# Hypnos_V2.net
KiCad netlist of a schematic drawn in EAGLE
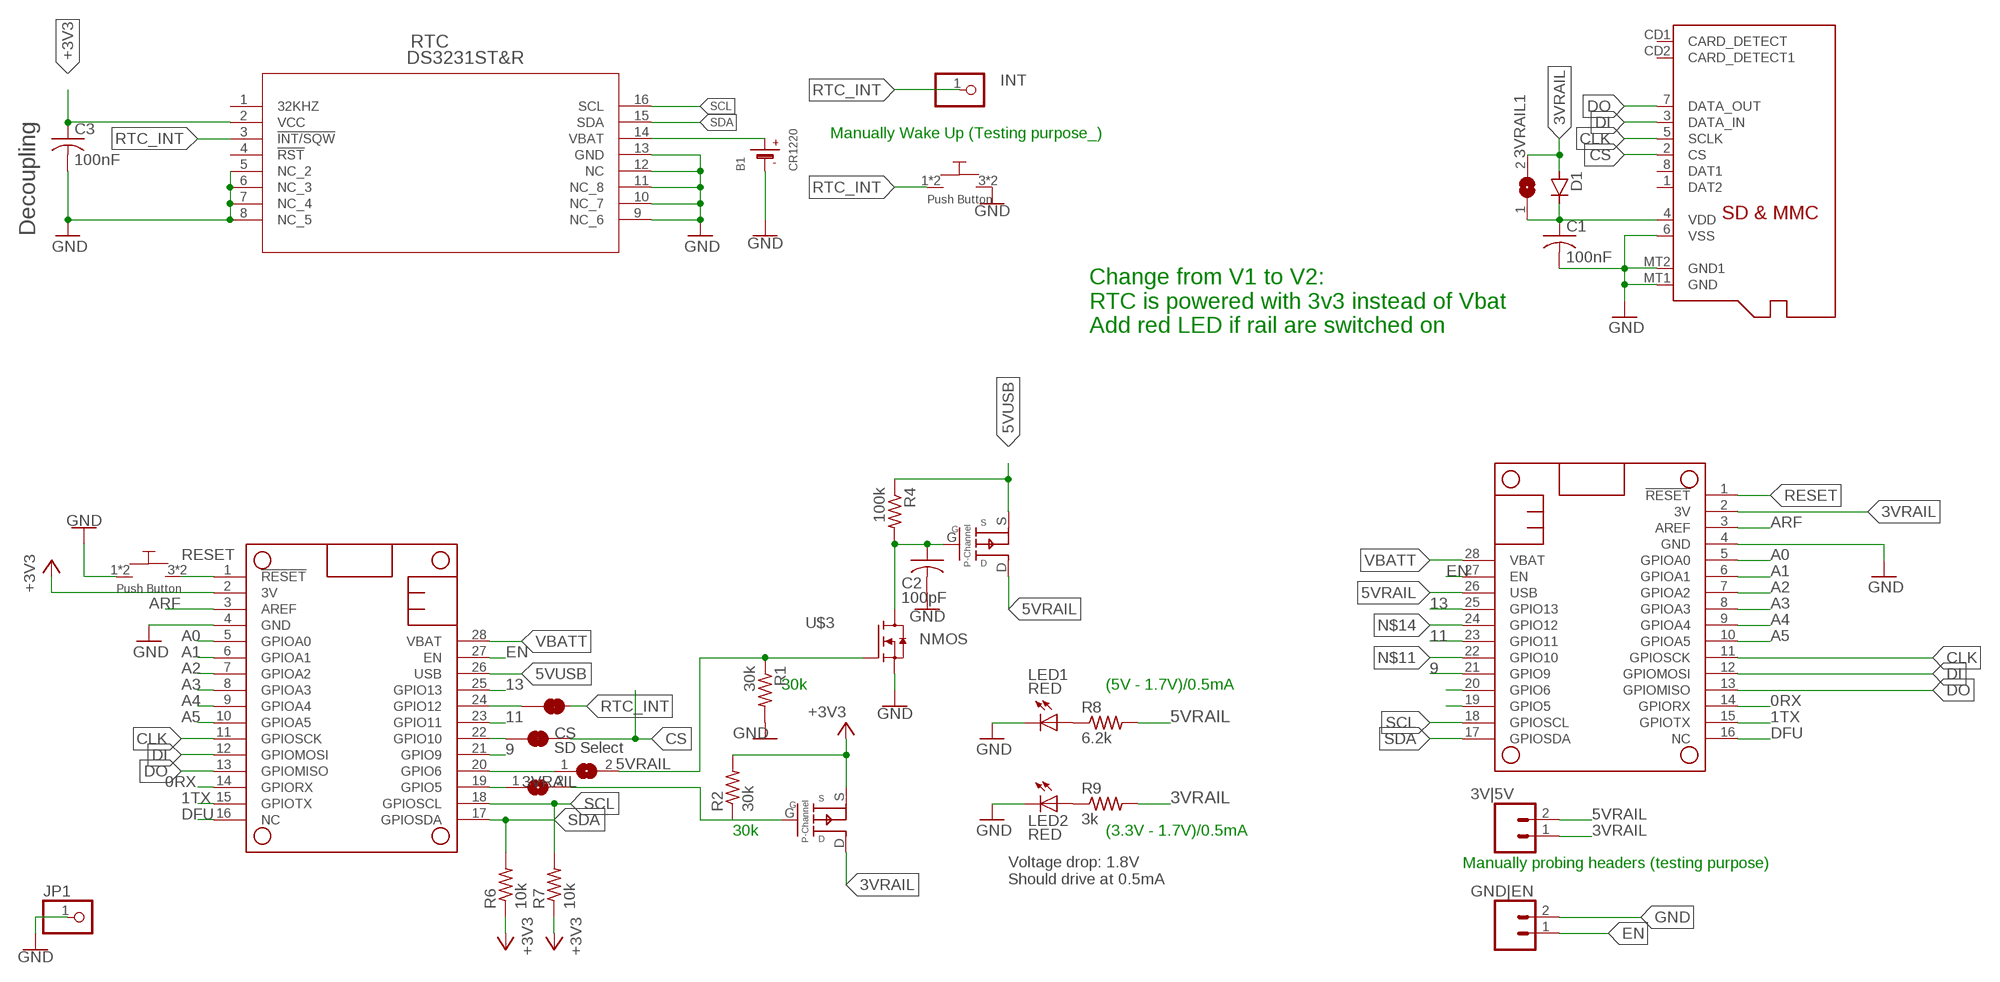
[diagram p0: schematic, sheet 1]

(export (version "E")
  (design (tool "Eeschema 10.0.6"))
  (components
    (comp (ref "3VRAIL")
      (value "SJ")
      (footprint "eagle-import:SJ")
      (libsource (lib "eagle-import") (part "SJ"))
    )
    (comp (ref "3VRAIL1")
      (value "SJ")
      (footprint "eagle-import:SJ")
      (libsource (lib "eagle-import") (part "SJ"))
    )
    (comp (ref "3V|5V")
      (value "CONN_021X02_NO_SILK")
      (footprint "eagle-import:1X02_NO_SILK")
      (libsource (lib "eagle-import") (part "CONN_021X02_NO_SILK"))
    )
    (comp (ref "5VRAIL")
      (value "SJ")
      (footprint "eagle-import:SJ")
      (libsource (lib "eagle-import") (part "SJ"))
    )
    (comp (ref "B1")
      (value "CR1220")
      (footprint "eagle-import:CR1220")
      (libsource (lib "eagle-import") (part "BATTERYCR1220_SMT"))
    )
    (comp (ref "C1")
      (value "100nF")
      (footprint "eagle-import:C1206")
      (libsource (lib "eagle-import") (part "C-USC1206"))
    )
    (comp (ref "C2")
      (value "100pF")
      (footprint "eagle-import:C0805")
      (libsource (lib "eagle-import") (part "C-USC0805"))
    )
    (comp (ref "C3")
      (value "100nF")
      (footprint "eagle-import:C1206")
      (libsource (lib "eagle-import") (part "C-USC1206"))
    )
    (comp (ref "CS")
      (value "SD Select")
      (footprint "eagle-import:SMT-JUMPER_2_NC_TRACE_SILK")
      (libsource (lib "eagle-import") (part "JUMPER-SMT_2_NC_TRACE_SILK"))
    )
    (comp (ref "D1")
      (value "D-SOD123")
      (footprint "eagle-import:SOD123")
      (libsource (lib "eagle-import") (part "D-SOD123"))
    )
    (comp (ref "GND|EN")
      (value "CONN_021X02_NO_SILK")
      (footprint "eagle-import:1X02_NO_SILK")
      (libsource (lib "eagle-import") (part "CONN_021X02_NO_SILK"))
    )
    (comp (ref "INT")
      (value "PINHD-1X1CB")
      (footprint "eagle-import:1X01-CLEANBIG")
      (libsource (lib "eagle-import") (part "PINHD-1X1CB"))
    )
    (comp (ref "JP1")
      (value "PINHD-1X1CB")
      (footprint "eagle-import:1X01-CLEANBIG")
      (libsource (lib "eagle-import") (part "PINHD-1X1CB"))
    )
    (comp (ref "LED1")
      (value "RED")
      (footprint "eagle-import:CHIPLED_0805")
      (libsource (lib "eagle-import") (part "LEDCHIPLED_0805"))
    )
    (comp (ref "LED2")
      (value "RED")
      (footprint "eagle-import:CHIPLED_0805")
      (libsource (lib "eagle-import") (part "LEDCHIPLED_0805"))
    )
    (comp (ref "MICROSD")
      (value "MICROSD")
      (footprint "eagle-import:MICROSD")
      (libsource (lib "eagle-import") (part "MICROSD"))
    )
    (comp (ref "MS1")
      (value "FEATHERWING")
      (footprint "eagle-import:FEATHERWING")
      (libsource (lib "eagle-import") (part "powerboard_FEATHERWING"))
    )
    (comp (ref "MS2")
      (value "FEATHERWING")
      (footprint "eagle-import:FEATHERWING")
      (libsource (lib "eagle-import") (part "FEATHERWING"))
    )
    (comp (ref "PMOS1")
      (value "SSM3J3228R")
      (footprint "eagle-import:SOT-23-3")
      (libsource (lib "eagle-import") (part "SSM3J3228R"))
    )
    (comp (ref "PMOS2")
      (value "SSM3J3228R")
      (footprint "eagle-import:SOT-23-3")
      (libsource (lib "eagle-import") (part "SSM3J3228R"))
    )
    (comp (ref "R1")
      (value "30k")
      (footprint "eagle-import:RES_1206")
      (fields
        (field (name "DIGIKEY_PART_NUMBER") "WSLP-.05TR-ND")
        (field (name "MANUFACTURER") "Vishay Dale")
        (field (name "MPN") "WSLP1206R0500FEA")
        (field (name "CREATED_BY") "PCBLayout.com")
      )
      (libsource (lib "eagle-import") (part "WSLP1206R0500FEA"))
    )
    (comp (ref "R2")
      (value "30k")
      (footprint "eagle-import:RES_1206")
      (fields
        (field (name "DIGIKEY_PART_NUMBER") "WSLP-.05TR-ND")
        (field (name "MANUFACTURER") "Vishay Dale")
        (field (name "MPN") "WSLP1206R0500FEA")
        (field (name "CREATED_BY") "PCBLayout.com")
      )
      (libsource (lib "eagle-import") (part "WSLP1206R0500FEA"))
    )
    (comp (ref "R4")
      (value "100k")
      (footprint "eagle-import:RES_1206")
      (fields
        (field (name "DIGIKEY_PART_NUMBER") "WSLP-.05TR-ND")
        (field (name "MANUFACTURER") "Vishay Dale")
        (field (name "MPN") "WSLP1206R0500FEA")
        (field (name "CREATED_BY") "PCBLayout.com")
      )
      (libsource (lib "eagle-import") (part "WSLP1206R0500FEA"))
    )
    (comp (ref "R6")
      (value "10k")
      (footprint "eagle-import:RES_1206")
      (fields
        (field (name "DIGIKEY_PART_NUMBER") "WSLP-.05TR-ND")
        (field (name "MANUFACTURER") "Vishay Dale")
        (field (name "MPN") "WSLP1206R0500FEA")
        (field (name "CREATED_BY") "PCBLayout.com")
      )
      (libsource (lib "eagle-import") (part "WSLP1206R0500FEA"))
    )
    (comp (ref "R7")
      (value "10k")
      (footprint "eagle-import:RES_1206")
      (fields
        (field (name "DIGIKEY_PART_NUMBER") "WSLP-.05TR-ND")
        (field (name "MANUFACTURER") "Vishay Dale")
        (field (name "MPN") "WSLP1206R0500FEA")
        (field (name "CREATED_BY") "PCBLayout.com")
      )
      (libsource (lib "eagle-import") (part "WSLP1206R0500FEA"))
    )
    (comp (ref "R8")
      (value "6.2k")
      (footprint "eagle-import:RES_1206")
      (fields
        (field (name "DIGIKEY_PART_NUMBER") "WSLP-.05TR-ND")
        (field (name "MANUFACTURER") "Vishay Dale")
        (field (name "MPN") "WSLP1206R0500FEA")
        (field (name "CREATED_BY") "PCBLayout.com")
      )
      (libsource (lib "eagle-import") (part "WSLP1206R0500FEA"))
    )
    (comp (ref "R9")
      (value "3k")
      (footprint "eagle-import:RES_1206")
      (fields
        (field (name "DIGIKEY_PART_NUMBER") "WSLP-.05TR-ND")
        (field (name "MANUFACTURER") "Vishay Dale")
        (field (name "MPN") "WSLP1206R0500FEA")
        (field (name "CREATED_BY") "PCBLayout.com")
      )
      (libsource (lib "eagle-import") (part "WSLP1206R0500FEA"))
    )
    (comp (ref "RTC")
      (value "DS3231ST&R")
      (footprint "eagle-import:21-0042B_16")
      (fields (field (name "MANUFACTURER_PART_NUMBER") "DS3231S#T&R"))
      (libsource (lib "eagle-import") (part "DS3231ST&R"))
    )
    (comp (ref "RTC_INT")
      (value "JUMPER-SMT_2_NC_TRACE_SILK")
      (footprint "eagle-import:SMT-JUMPER_2_NC_TRACE_SILK")
      (libsource (lib "eagle-import") (part "JUMPER-SMT_2_NC_TRACE_SILK"))
    )
    (comp (ref "U$1")
      (value "PUSH_BUTTON")
      (footprint "eagle-import:PUSHBUTTON_SMD")
      (libsource (lib "eagle-import") (part "PUSH_BUTTON"))
    )
    (comp (ref "U$2")
      (value "PUSH_BUTTON")
      (footprint "eagle-import:PUSHBUTTON_SMD")
      (libsource (lib "eagle-import") (part "PUSH_BUTTON"))
    )
    (comp (ref "U$3")
      (value "NMOS")
      (footprint "eagle-import:SOT23-S")
      (libsource (lib "eagle-import") (part "NMOS"))
    )
  )
  (nets
    (net (code "1") (name "+3V3") (class "Default")
      (node (ref "C3") (pin "1") (pinfunction "1_1") (pintype "passive"))
      (node (ref "MS2") (pin "2") (pinfunction "3V_2") (pintype "power_in"))
      (node (ref "PMOS2") (pin "S") (pinfunction "S_S") (pintype "bidirectional"))
      (node (ref "R2") (pin "2") (pinfunction "2_2") (pintype "passive"))
      (node (ref "R6") (pin "1") (pinfunction "1_1") (pintype "passive"))
      (node (ref "R7") (pin "1") (pinfunction "1_1") (pintype "passive"))
      (node (ref "RTC") (pin "2") (pinfunction "VCC_2") (pintype "power_in"))
    )
    (net (code "2") (name "/0RX") (class "Default")
      (node (ref "MS1") (pin "14") (pinfunction "GPIORX_14") (pintype "bidirectional"))
      (node (ref "MS2") (pin "14") (pinfunction "GPIORX_14") (pintype "bidirectional"))
    )
    (net (code "3") (name "/1TX") (class "Default")
      (node (ref "MS1") (pin "15") (pinfunction "GPIOTX_15") (pintype "bidirectional"))
      (node (ref "MS2") (pin "15") (pinfunction "GPIOTX_15") (pintype "bidirectional"))
    )
    (net (code "4") (name "/9") (class "Default")
      (node (ref "MS1") (pin "21") (pinfunction "GPIO9_21") (pintype "bidirectional"))
      (node (ref "MS2") (pin "21") (pinfunction "GPIO9_21") (pintype "bidirectional"))
    )
    (net (code "5") (name "/11") (class "Default")
      (node (ref "MS1") (pin "23") (pinfunction "GPIO11_23") (pintype "bidirectional"))
      (node (ref "MS2") (pin "23") (pinfunction "GPIO11_23") (pintype "bidirectional"))
    )
    (net (code "6") (name "/13") (class "Default")
      (node (ref "MS1") (pin "25") (pinfunction "GPIO13_25") (pintype "bidirectional"))
      (node (ref "MS2") (pin "25") (pinfunction "GPIO13_25") (pintype "bidirectional"))
    )
    (net (code "7") (name "/A0") (class "Default")
      (node (ref "MS1") (pin "5") (pinfunction "GPIOA0_5") (pintype "bidirectional"))
      (node (ref "MS2") (pin "5") (pinfunction "GPIOA0_5") (pintype "bidirectional"))
    )
    (net (code "8") (name "/A1") (class "Default")
      (node (ref "MS1") (pin "6") (pinfunction "GPIOA1_6") (pintype "bidirectional"))
      (node (ref "MS2") (pin "6") (pinfunction "GPIOA1_6") (pintype "bidirectional"))
    )
    (net (code "9") (name "/A2") (class "Default")
      (node (ref "MS1") (pin "7") (pinfunction "GPIOA2_7") (pintype "bidirectional"))
      (node (ref "MS2") (pin "7") (pinfunction "GPIOA2_7") (pintype "bidirectional"))
    )
    (net (code "10") (name "/A3") (class "Default")
      (node (ref "MS1") (pin "8") (pinfunction "GPIOA3_8") (pintype "bidirectional"))
      (node (ref "MS2") (pin "8") (pinfunction "GPIOA3_8") (pintype "bidirectional"))
    )
    (net (code "11") (name "/A4") (class "Default")
      (node (ref "MS1") (pin "9") (pinfunction "GPIOA4_9") (pintype "bidirectional"))
      (node (ref "MS2") (pin "9") (pinfunction "GPIOA4_9") (pintype "bidirectional"))
    )
    (net (code "12") (name "/A5") (class "Default")
      (node (ref "MS1") (pin "10") (pinfunction "GPIOA5_10") (pintype "bidirectional"))
      (node (ref "MS2") (pin "10") (pinfunction "GPIOA5_10") (pintype "bidirectional"))
    )
    (net (code "13") (name "/ARF") (class "Default")
      (node (ref "MS1") (pin "3") (pinfunction "AREF_3") (pintype "passive"))
      (node (ref "MS2") (pin "3") (pinfunction "AREF_3") (pintype "passive"))
    )
    (net (code "14") (name "/DFU") (class "Default")
      (node (ref "MS1") (pin "16") (pinfunction "NC_16") (pintype "passive"))
      (node (ref "MS2") (pin "16") (pinfunction "NC_16") (pintype "passive"))
    )
    (net (code "15") (name "3VRAIL") (class "Default")
      (node (ref "3VRAIL1") (pin "2") (pinfunction "2_2") (pintype "passive"))
      (node (ref "3V|5V") (pin "1") (pinfunction "1_1") (pintype "passive"))
      (node (ref "D1") (pin "2") (pinfunction "A_2") (pintype "passive"))
      (node (ref "MS1") (pin "2") (pinfunction "3V_2") (pintype "power_in"))
      (node (ref "PMOS2") (pin "D") (pinfunction "D_D") (pintype "bidirectional"))
      (node (ref "R9") (pin "2") (pinfunction "2_2") (pintype "passive"))
    )
    (net (code "16") (name "5VRAIL") (class "Default")
      (node (ref "3V|5V") (pin "2") (pinfunction "2_2") (pintype "passive"))
      (node (ref "MS1") (pin "26") (pinfunction "USB_26") (pintype "power_in"))
      (node (ref "PMOS1") (pin "D") (pinfunction "D_D") (pintype "bidirectional"))
      (node (ref "R8") (pin "2") (pinfunction "2_2") (pintype "passive"))
    )
    (net (code "17") (name "5VUSB") (class "Default")
      (node (ref "MS2") (pin "26") (pinfunction "USB_26") (pintype "power_in"))
      (node (ref "PMOS1") (pin "S") (pinfunction "S_S") (pintype "bidirectional"))
      (node (ref "R4") (pin "1") (pinfunction "1_1") (pintype "passive"))
    )
    (net (code "18") (name "CLK") (class "Default")
      (node (ref "MICROSD") (pin "5") (pinfunction "SCLK_5") (pintype "input"))
      (node (ref "MS1") (pin "11") (pinfunction "GPIOSCK_11") (pintype "bidirectional"))
      (node (ref "MS2") (pin "11") (pinfunction "GPIOSCK_11") (pintype "bidirectional"))
    )
    (net (code "19") (name "CS") (class "Default")
      (node (ref "CS") (pin "2") (pinfunction "2_2") (pintype "passive"))
      (node (ref "MICROSD") (pin "2") (pinfunction "CS_2") (pintype "input"))
    )
    (net (code "20") (name "DI") (class "Default")
      (node (ref "MICROSD") (pin "3") (pinfunction "DATA_IN_3") (pintype "input"))
      (node (ref "MS1") (pin "12") (pinfunction "GPIOMOSI_12") (pintype "bidirectional"))
      (node (ref "MS2") (pin "12") (pinfunction "GPIOMOSI_12") (pintype "bidirectional"))
    )
    (net (code "21") (name "DO") (class "Default")
      (node (ref "MICROSD") (pin "7") (pinfunction "DATA_OUT_7") (pintype "output"))
      (node (ref "MS1") (pin "13") (pinfunction "GPIOMISO_13") (pintype "bidirectional"))
      (node (ref "MS2") (pin "13") (pinfunction "GPIOMISO_13") (pintype "bidirectional"))
    )
    (net (code "22") (name "EN") (class "Default")
      (node (ref "GND|EN") (pin "1") (pinfunction "1_1") (pintype "passive"))
      (node (ref "MS1") (pin "27") (pinfunction "EN_27") (pintype "passive"))
      (node (ref "MS2") (pin "27") (pinfunction "EN_27") (pintype "passive"))
    )
    (net (code "23") (name "GND") (class "Default")
      (node (ref "B1") (pin "-") (pinfunction "-_-") (pintype "passive"))
      (node (ref "C1") (pin "2") (pinfunction "2_2") (pintype "passive"))
      (node (ref "C2") (pin "2") (pinfunction "2_2") (pintype "passive"))
      (node (ref "C3") (pin "2") (pinfunction "2_2") (pintype "passive"))
      (node (ref "GND|EN") (pin "2") (pinfunction "2_2") (pintype "passive"))
      (node (ref "JP1") (pin "1") (pinfunction "1_1") (pintype "passive"))
      (node (ref "LED1") (pin "C") (pinfunction "C_C") (pintype "passive"))
      (node (ref "LED2") (pin "C") (pinfunction "C_C") (pintype "passive"))
      (node (ref "MICROSD") (pin "6") (pinfunction "VSS_6") (pintype "power_in"))
      (node (ref "MICROSD") (pin "MT1") (pinfunction "GND_MT1") (pintype "power_in"))
      (node (ref "MICROSD") (pin "MT2") (pinfunction "GND1_MT2") (pintype "power_in"))
      (node (ref "MS1") (pin "4") (pinfunction "GND_4") (pintype "power_in"))
      (node (ref "MS2") (pin "4") (pinfunction "GND_4") (pintype "power_in"))
      (node (ref "R1") (pin "2") (pinfunction "2_2") (pintype "passive"))
      (node (ref "RTC") (pin "10") (pinfunction "NC_7_10") (pintype "passive"))
      (node (ref "RTC") (pin "11") (pinfunction "NC_8_11") (pintype "passive"))
      (node (ref "RTC") (pin "12") (pinfunction "NC_12") (pintype "passive"))
      (node (ref "RTC") (pin "13") (pinfunction "GND_13") (pintype "power_in"))
      (node (ref "RTC") (pin "5") (pinfunction "NC_2_5") (pintype "passive"))
      (node (ref "RTC") (pin "6") (pinfunction "NC_3_6") (pintype "passive"))
      (node (ref "RTC") (pin "7") (pinfunction "NC_4_7") (pintype "passive"))
      (node (ref "RTC") (pin "8") (pinfunction "NC_5_8") (pintype "passive"))
      (node (ref "RTC") (pin "9") (pinfunction "NC_6_9") (pintype "passive"))
      (node (ref "U$1") (pin "1") (pinfunction "P$1_1") (pintype "bidirectional"))
      (node (ref "U$1") (pin "2") (pinfunction "P$1_2") (pintype "bidirectional"))
      (node (ref "U$2") (pin "3") (pinfunction "P$2_3") (pintype "bidirectional"))
      (node (ref "U$2") (pin "4") (pinfunction "P$2_4") (pintype "bidirectional"))
      (node (ref "U$3") (pin "2") (pinfunction "S_2") (pintype "passive"))
    )
    (net (code "24") (name "N$11") (class "Default")
      (node (ref "CS") (pin "1") (pinfunction "1_1") (pintype "passive"))
      (node (ref "MS1") (pin "22") (pinfunction "GPIO10_22") (pintype "bidirectional"))
      (node (ref "MS2") (pin "22") (pinfunction "GPIO10_22") (pintype "bidirectional"))
    )
    (net (code "25") (name "N$14") (class "Default")
      (node (ref "MS1") (pin "24") (pinfunction "GPIO12_24") (pintype "bidirectional"))
      (node (ref "MS2") (pin "24") (pinfunction "GPIO12_24") (pintype "bidirectional"))
      (node (ref "RTC_INT") (pin "1") (pinfunction "1_1") (pintype "passive"))
    )
    (net (code "26") (name "Net-(3VRAIL-Pad2)") (class "Default")
      (node (ref "3VRAIL") (pin "2") (pinfunction "2_2") (pintype "passive"))
      (node (ref "PMOS2") (pin "G") (pinfunction "G_G") (pintype "bidirectional"))
      (node (ref "R2") (pin "1") (pinfunction "1_1") (pintype "passive"))
    )
    (net (code "27") (name "Net-(B1-+)") (class "Default")
      (node (ref "B1") (pin "+$1") (pinfunction "+_+$1") (pintype "passive"))
      (node (ref "RTC") (pin "14") (pinfunction "VBAT_14") (pintype "power_in"))
    )
    (net (code "28") (name "Net-(D1-C)") (class "Default")
      (node (ref "3VRAIL1") (pin "1") (pinfunction "1_1") (pintype "passive"))
      (node (ref "C1") (pin "1") (pinfunction "1_1") (pintype "passive"))
      (node (ref "D1") (pin "1") (pinfunction "C_1") (pintype "passive"))
      (node (ref "MICROSD") (pin "4") (pinfunction "VDD_4") (pintype "power_in"))
    )
    (net (code "29") (name "Net-(LED1-PadA)") (class "Default")
      (node (ref "LED1") (pin "A") (pinfunction "A_A") (pintype "passive"))
      (node (ref "R8") (pin "1") (pinfunction "1_1") (pintype "passive"))
    )
    (net (code "30") (name "Net-(LED2-PadA)") (class "Default")
      (node (ref "LED2") (pin "A") (pinfunction "A_A") (pintype "passive"))
      (node (ref "R9") (pin "1") (pinfunction "1_1") (pintype "passive"))
    )
    (net (code "31") (name "Net-(MS2-GPIO5)") (class "Default")
      (node (ref "3VRAIL") (pin "1") (pinfunction "1_1") (pintype "passive"))
      (node (ref "MS2") (pin "19") (pinfunction "GPIO5_19") (pintype "bidirectional"))
    )
    (net (code "32") (name "Net-(MS2-GPIO6)") (class "Default")
      (node (ref "5VRAIL") (pin "1") (pinfunction "1_1") (pintype "passive"))
      (node (ref "MS2") (pin "20") (pinfunction "GPIO6_20") (pintype "bidirectional"))
    )
    (net (code "33") (name "Net-(U$3-D)") (class "Default")
      (node (ref "C2") (pin "1") (pinfunction "1_1") (pintype "passive"))
      (node (ref "PMOS1") (pin "G") (pinfunction "G_G") (pintype "bidirectional"))
      (node (ref "R4") (pin "2") (pinfunction "2_2") (pintype "passive"))
      (node (ref "U$3") (pin "3") (pinfunction "D_3") (pintype "passive"))
    )
    (net (code "34") (name "Net-(U$3-G)") (class "Default")
      (node (ref "5VRAIL") (pin "2") (pinfunction "2_2") (pintype "passive"))
      (node (ref "R1") (pin "1") (pinfunction "1_1") (pintype "passive"))
      (node (ref "U$3") (pin "1") (pinfunction "G_1") (pintype "passive"))
    )
    (net (code "35") (name "RESET") (class "Default")
      (node (ref "MS1") (pin "1") (pinfunction "~{RESET}_1") (pintype "input"))
      (node (ref "MS2") (pin "1") (pinfunction "~{RESET}_1") (pintype "input"))
      (node (ref "U$1") (pin "3") (pinfunction "P$2_3") (pintype "bidirectional"))
      (node (ref "U$1") (pin "4") (pinfunction "P$2_4") (pintype "bidirectional"))
    )
    (net (code "36") (name "RTC_INT") (class "Default")
      (node (ref "INT") (pin "1") (pinfunction "1_1") (pintype "passive"))
      (node (ref "RTC") (pin "3") (pinfunction "~{INT/SQW}_3") (pintype "passive"))
      (node (ref "RTC_INT") (pin "2") (pinfunction "2_2") (pintype "passive"))
      (node (ref "U$2") (pin "1") (pinfunction "P$1_1") (pintype "bidirectional"))
      (node (ref "U$2") (pin "2") (pinfunction "P$1_2") (pintype "bidirectional"))
    )
    (net (code "37") (name "SCL") (class "Default")
      (node (ref "MS1") (pin "18") (pinfunction "GPIOSCL_18") (pintype "bidirectional"))
      (node (ref "MS2") (pin "18") (pinfunction "GPIOSCL_18") (pintype "bidirectional"))
      (node (ref "R7") (pin "2") (pinfunction "2_2") (pintype "passive"))
      (node (ref "RTC") (pin "16") (pinfunction "SCL_16") (pintype "passive"))
    )
    (net (code "38") (name "SDA") (class "Default")
      (node (ref "MS1") (pin "17") (pinfunction "GPIOSDA_17") (pintype "bidirectional"))
      (node (ref "MS2") (pin "17") (pinfunction "GPIOSDA_17") (pintype "bidirectional"))
      (node (ref "R6") (pin "2") (pinfunction "2_2") (pintype "passive"))
      (node (ref "RTC") (pin "15") (pinfunction "SDA_15") (pintype "passive"))
    )
    (net (code "39") (name "VBATT") (class "Default")
      (node (ref "MS1") (pin "28") (pinfunction "VBAT_28") (pintype "power_in"))
      (node (ref "MS2") (pin "28") (pinfunction "VBAT_28") (pintype "power_in"))
    )
    (net (code "40") (name "unconnected-(MICROSD-CARD_DETECT-PadCD1)") (class "Default")
      (node (ref "MICROSD") (pin "CD1") (pinfunction "CARD_DETECT_CD1") (pintype "passive"))
    )
    (net (code "41") (name "unconnected-(MICROSD-CARD_DETECT1-PadCD2)") (class "Default")
      (node (ref "MICROSD") (pin "CD2") (pinfunction "CARD_DETECT1_CD2") (pintype "passive"))
    )
    (net (code "42") (name "unconnected-(MICROSD-DAT1-Pad8)") (class "Default")
      (node (ref "MICROSD") (pin "8") (pinfunction "DAT1_8") (pintype "bidirectional"))
    )
    (net (code "43") (name "unconnected-(MICROSD-DAT2-Pad1)") (class "Default")
      (node (ref "MICROSD") (pin "1") (pinfunction "DAT2_1") (pintype "bidirectional"))
    )
    (net (code "44") (name "unconnected-(MS1-GPIO5-Pad19)") (class "Default")
      (node (ref "MS1") (pin "19") (pinfunction "GPIO5_19") (pintype "bidirectional"))
    )
    (net (code "45") (name "unconnected-(MS1-GPIO6-Pad20)") (class "Default")
      (node (ref "MS1") (pin "20") (pinfunction "GPIO6_20") (pintype "bidirectional"))
    )
    (net (code "46") (name "unconnected-(RTC-32KHZ-Pad1)") (class "Default")
      (node (ref "RTC") (pin "1") (pinfunction "32KHZ_1") (pintype "passive"))
    )
    (net (code "47") (name "unconnected-(RTC-~{RST}-Pad4)") (class "Default")
      (node (ref "RTC") (pin "4") (pinfunction "~{RST}_4") (pintype "passive"))
    )
  )
)
